# Cook_It.net
KiCad netlist of a schematic drawn in Altium Designer
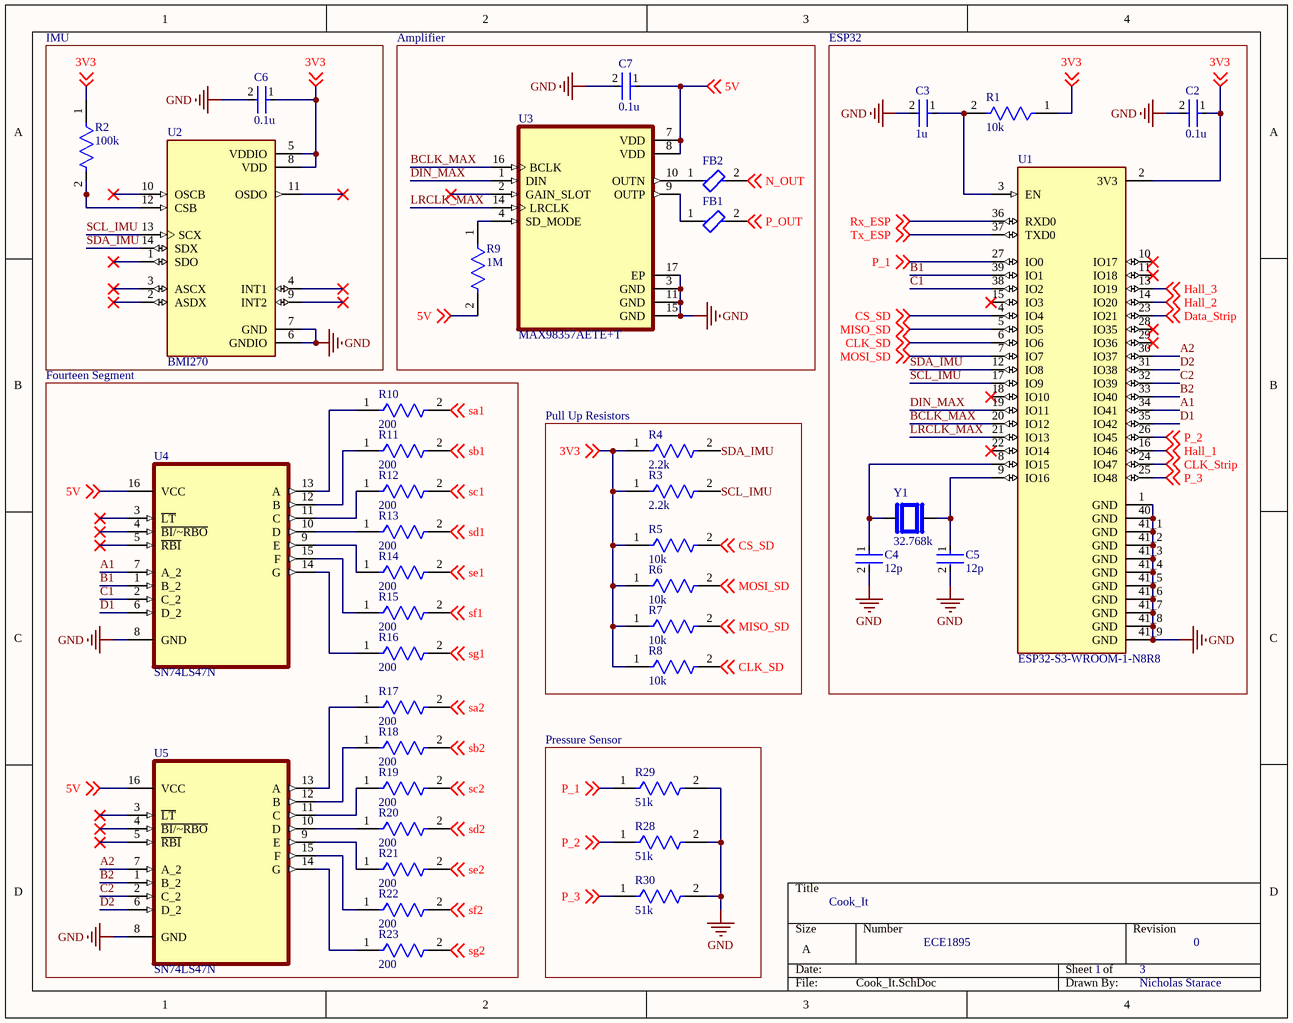
[diagram p0: Cook_It.SchDoc]

(export (version "E")
  (design (tool "Eeschema 10.0.6"))
  (components
    (comp (ref "C2")
      (value "0.1u")
      (footprint "FP-GRM21B-0_2-e0_2_0_7-IPC_B")
      (description "CAP CER 2.2UF 100V X7T 0805")
      (libsource (lib "Altium Content Vault") (part "b4654b650e69147ec39a6b967a45e02"))
    )
    (comp (ref "C3")
      (value "1u")
      (footprint "FP-GRM21B-0_2-e0_2_0_7-IPC_B")
      (description "CAP CER 2.2UF 100V X7T 0805")
      (libsource (lib "Altium Content Vault") (part "b4654b650e69147ec39a6b967a45e02"))
    )
    (comp (ref "C4")
      (value "12p")
      (footprint "FP-GRM21B-0_2-e0_2_0_7-IPC_B")
      (description "CAP CER 2.2UF 100V X7T 0805")
      (libsource (lib "Altium Content Vault") (part "b4654b650e69147ec39a6b967a45e02"))
    )
    (comp (ref "C5")
      (value "12p")
      (footprint "FP-GRM21B-0_2-e0_2_0_7-IPC_B")
      (description "CAP CER 2.2UF 100V X7T 0805")
      (libsource (lib "Altium Content Vault") (part "b4654b650e69147ec39a6b967a45e02"))
    )
    (comp (ref "C6")
      (value "0.1u")
      (footprint "FP-GRM21B-0_2-e0_2_0_7-IPC_B")
      (description "CAP CER 2.2UF 100V X7T 0805")
      (libsource (lib "Altium Content Vault") (part "b4654b650e69147ec39a6b967a45e02"))
    )
    (comp (ref "C7")
      (value "0.1u")
      (footprint "FP-GRM21B-0_2-e0_2_0_7-IPC_B")
      (description "CAP CER 2.2UF 100V X7T 0805")
      (libsource (lib "Altium Content Vault") (part "b4654b650e69147ec39a6b967a45e02"))
    )
    (comp (ref "FB1")
      (value "~")
      (footprint "FP-BMB2A1000LN2-IPC_C")
      (description "FERRITE BEAD 1 KOHM 0805 1LN")
      (fields (field (name "TOLERANCE") "25%"))
      (libsource (lib "Altium Content Vault") (part "5f30dd21d616792df468990f7003faa"))
    )
    (comp (ref "FB2")
      (value "~")
      (footprint "FP-BMB2A1000LN2-IPC_C")
      (description "FERRITE BEAD 1 KOHM 0805 1LN")
      (fields (field (name "TOLERANCE") "25%"))
      (libsource (lib "Altium Content Vault") (part "5f30dd21d616792df468990f7003faa"))
    )
    (comp (ref "R1")
      (value "10k")
      (footprint "FP-TFCR0805-IPC_B")
      (description "RES Thin Film,  499kΩ, 0.1%, 0.125W, 25ppm/°C, 0805")
      (libsource (lib "Altium Content Vault") (part "1029c3af85768c4190bb7ad29bc67b5"))
    )
    (comp (ref "R2")
      (value "100k")
      (footprint "FP-TFCR0805-IPC_B")
      (description "RES Thin Film,  499kΩ, 0.1%, 0.125W, 25ppm/°C, 0805")
      (libsource (lib "Altium Content Vault") (part "1029c3af85768c4190bb7ad29bc67b5"))
    )
    (comp (ref "R3")
      (value "2.2k")
      (footprint "FP-TFCR0805-IPC_B")
      (description "RES Thin Film,  499kΩ, 0.1%, 0.125W, 25ppm/°C, 0805")
      (libsource (lib "Altium Content Vault") (part "1029c3af85768c4190bb7ad29bc67b5"))
    )
    (comp (ref "R4")
      (value "2.2k")
      (footprint "FP-TFCR0805-IPC_B")
      (description "RES Thin Film,  499kΩ, 0.1%, 0.125W, 25ppm/°C, 0805")
      (libsource (lib "Altium Content Vault") (part "1029c3af85768c4190bb7ad29bc67b5"))
    )
    (comp (ref "R5")
      (value "10k")
      (footprint "FP-TFCR0805-IPC_B")
      (description "RES Thin Film,  499kΩ, 0.1%, 0.125W, 25ppm/°C, 0805")
      (libsource (lib "Altium Content Vault") (part "1029c3af85768c4190bb7ad29bc67b5"))
    )
    (comp (ref "R6")
      (value "10k")
      (footprint "FP-TFCR0805-IPC_B")
      (description "RES Thin Film,  499kΩ, 0.1%, 0.125W, 25ppm/°C, 0805")
      (libsource (lib "Altium Content Vault") (part "1029c3af85768c4190bb7ad29bc67b5"))
    )
    (comp (ref "R7")
      (value "10k")
      (footprint "FP-TFCR0805-IPC_B")
      (description "RES Thin Film,  499kΩ, 0.1%, 0.125W, 25ppm/°C, 0805")
      (libsource (lib "Altium Content Vault") (part "1029c3af85768c4190bb7ad29bc67b5"))
    )
    (comp (ref "R8")
      (value "10k")
      (footprint "FP-TFCR0805-IPC_B")
      (description "RES Thin Film,  499kΩ, 0.1%, 0.125W, 25ppm/°C, 0805")
      (libsource (lib "Altium Content Vault") (part "1029c3af85768c4190bb7ad29bc67b5"))
    )
    (comp (ref "R9")
      (value "1M")
      (footprint "FP-TFCR0805-IPC_B")
      (description "RES Thin Film,  499kΩ, 0.1%, 0.125W, 25ppm/°C, 0805")
      (libsource (lib "Altium Content Vault") (part "1029c3af85768c4190bb7ad29bc67b5"))
    )
    (comp (ref "R10")
      (value "200")
      (footprint "FP-TFCR0805-MFG")
      (description "RES Thin Film,  1.72kΩ, 1%, 0.125W, 25ppm/°C, 0805")
      (libsource (lib "Altium Content Vault") (part "1029c3af85768c4190bb7ad29bc67b5"))
    )
    (comp (ref "R11")
      (value "200")
      (footprint "FP-TFCR0805-MFG")
      (description "RES Thin Film,  1.72kΩ, 1%, 0.125W, 25ppm/°C, 0805")
      (libsource (lib "Altium Content Vault") (part "1029c3af85768c4190bb7ad29bc67b5"))
    )
    (comp (ref "R12")
      (value "200")
      (footprint "FP-TFCR0805-MFG")
      (description "RES Thin Film,  1.72kΩ, 1%, 0.125W, 25ppm/°C, 0805")
      (libsource (lib "Altium Content Vault") (part "1029c3af85768c4190bb7ad29bc67b5"))
    )
    (comp (ref "R13")
      (value "200")
      (footprint "FP-TFCR0805-MFG")
      (description "RES Thin Film,  1.72kΩ, 1%, 0.125W, 25ppm/°C, 0805")
      (libsource (lib "Altium Content Vault") (part "1029c3af85768c4190bb7ad29bc67b5"))
    )
    (comp (ref "R14")
      (value "200")
      (footprint "FP-TFCR0805-MFG")
      (description "RES Thin Film,  1.72kΩ, 1%, 0.125W, 25ppm/°C, 0805")
      (libsource (lib "Altium Content Vault") (part "1029c3af85768c4190bb7ad29bc67b5"))
    )
    (comp (ref "R15")
      (value "200")
      (footprint "FP-TFCR0805-MFG")
      (description "RES Thin Film,  1.72kΩ, 1%, 0.125W, 25ppm/°C, 0805")
      (libsource (lib "Altium Content Vault") (part "1029c3af85768c4190bb7ad29bc67b5"))
    )
    (comp (ref "R16")
      (value "200")
      (footprint "FP-TFCR0805-MFG")
      (description "RES Thin Film,  1.72kΩ, 1%, 0.125W, 25ppm/°C, 0805")
      (libsource (lib "Altium Content Vault") (part "1029c3af85768c4190bb7ad29bc67b5"))
    )
    (comp (ref "R17")
      (value "200")
      (footprint "FP-TFCR0805-MFG")
      (description "RES Thin Film,  1.72kΩ, 1%, 0.125W, 25ppm/°C, 0805")
      (libsource (lib "Altium Content Vault") (part "1029c3af85768c4190bb7ad29bc67b5"))
    )
    (comp (ref "R18")
      (value "200")
      (footprint "FP-TFCR0805-MFG")
      (description "RES Thin Film,  1.72kΩ, 1%, 0.125W, 25ppm/°C, 0805")
      (libsource (lib "Altium Content Vault") (part "1029c3af85768c4190bb7ad29bc67b5"))
    )
    (comp (ref "R19")
      (value "200")
      (footprint "FP-TFCR0805-MFG")
      (description "RES Thin Film,  1.72kΩ, 1%, 0.125W, 25ppm/°C, 0805")
      (libsource (lib "Altium Content Vault") (part "1029c3af85768c4190bb7ad29bc67b5"))
    )
    (comp (ref "R20")
      (value "200")
      (footprint "FP-TFCR0805-MFG")
      (description "RES Thin Film,  1.72kΩ, 1%, 0.125W, 25ppm/°C, 0805")
      (libsource (lib "Altium Content Vault") (part "1029c3af85768c4190bb7ad29bc67b5"))
    )
    (comp (ref "R21")
      (value "200")
      (footprint "FP-TFCR0805-MFG")
      (description "RES Thin Film,  1.72kΩ, 1%, 0.125W, 25ppm/°C, 0805")
      (libsource (lib "Altium Content Vault") (part "1029c3af85768c4190bb7ad29bc67b5"))
    )
    (comp (ref "R22")
      (value "200")
      (footprint "FP-TFCR0805-MFG")
      (description "RES Thin Film,  1.72kΩ, 1%, 0.125W, 25ppm/°C, 0805")
      (libsource (lib "Altium Content Vault") (part "1029c3af85768c4190bb7ad29bc67b5"))
    )
    (comp (ref "R23")
      (value "200")
      (footprint "FP-TFCR0805-MFG")
      (description "RES Thin Film,  1.72kΩ, 1%, 0.125W, 25ppm/°C, 0805")
      (libsource (lib "Altium Content Vault") (part "1029c3af85768c4190bb7ad29bc67b5"))
    )
    (comp (ref "R28")
      (value "51k")
      (footprint "FP-TFCR0805-IPC_B")
      (description "RES Thin Film,  499kΩ, 0.1%, 0.125W, 25ppm/°C, 0805")
      (libsource (lib "Altium Content Vault") (part "1029c3af85768c4190bb7ad29bc67b5"))
    )
    (comp (ref "R29")
      (value "51k")
      (footprint "FP-TFCR0805-IPC_B")
      (description "RES Thin Film,  499kΩ, 0.1%, 0.125W, 25ppm/°C, 0805")
      (libsource (lib "Altium Content Vault") (part "1029c3af85768c4190bb7ad29bc67b5"))
    )
    (comp (ref "R30")
      (value "51k")
      (footprint "FP-TFCR0805-IPC_B")
      (description "RES Thin Film,  499kΩ, 0.1%, 0.125W, 25ppm/°C, 0805")
      (libsource (lib "Altium Content Vault") (part "1029c3af85768c4190bb7ad29bc67b5"))
    )
    (comp (ref "U1")
      (value "ESP32-S3-WROOM-1-N8R8")
      (footprint "XCVR_ESP32S3WROOM1N8R8")
      (description "Bluetooth, WiFi 802.11b/g/n, Bluetooth v5.0 Transceiver Module 2.4GHz PCB Trace Surface Mount")
      (fields (field (name "MF") "Espressif Systems"))
      (libsource (lib "ESP32-S3-WROOM-1-N8R8") (part "ESP32-S3-WROOM-1-N8R8"))
    )
    (comp (ref "U2")
      (value "BMI270")
      (footprint "XDCR_BMI270")
      (description "Accelerometer, Gyroscope, 6 Axis Sensor IÂ²C, SPI Output")
      (fields (field (name "DIGI-KEY_PART_NUMBER") "828-1091-2-ND") (field (name "MF") "Bosch Sensortec"))
      (libsource (lib "BMI270") (part "BMI270"))
    )
    (comp (ref "U3")
      (value "MAX98357AETE+T")
      (footprint "QFN50P300X300X80-17N")
      (description "Tiny, Low-Cost, PCM Class D Amplifier with Class AB Performance")
      (fields (field (name "MF") "Analog Devices"))
      (libsource (lib "MAX98357AETE_T") (part "MAX98357AETE+T"))
    )
    (comp (ref "U4")
      (value "SN74LS47N")
      (footprint "SOIC127P600X175-16N")
      (description "Decoder/Driver Single 4-to-7 16-Pin PDIP Tube")
      (fields (field (name "MF") "onsemi"))
      (libsource (lib "SN74LS47N") (part "SN74LS47N"))
    )
    (comp (ref "U5")
      (value "SN74LS47N")
      (footprint "SOIC127P600X175-16N")
      (description "Decoder/Driver Single 4-to-7 16-Pin PDIP Tube")
      (fields (field (name "MF") "onsemi"))
      (libsource (lib "SN74LS47N") (part "SN74LS47N"))
    )
    (comp (ref "Y1")
      (value "32.768k")
      (footprint "XTAL_ABS07-32.768KHZ-T")
      (description "32.768 kHz Â±20ppm Crystal 12.5pF 70 kOhms 2-SMD, No Lead")
      (fields (field (name "MP") "ABS07-32.768KHZ-T") (field (name "MF") "Abracon"))
      (libsource (lib "ABS07-32.768KHZ-T") (part "ABS07-32.768KHZ-T"))
    )
  )
  (nets
    (net (code "1") (name "/A1") (class "Default")
      (node (ref "U1") (pin "34") (pinfunction "IO41_34") (pintype "bidirectional"))
      (node (ref "U4") (pin "7") (pinfunction "A_2_7") (pintype "input"))
    )
    (net (code "2") (name "/A2") (class "Default")
      (node (ref "U1") (pin "30") (pinfunction "IO37_30") (pintype "bidirectional"))
      (node (ref "U5") (pin "7") (pinfunction "A_2_7") (pintype "input"))
    )
    (net (code "3") (name "/B1") (class "Default")
      (node (ref "U1") (pin "39") (pinfunction "IO1_39") (pintype "bidirectional"))
      (node (ref "U4") (pin "1") (pinfunction "B_2_1") (pintype "input"))
    )
    (net (code "4") (name "/B2") (class "Default")
      (node (ref "U1") (pin "33") (pinfunction "IO40_33") (pintype "bidirectional"))
      (node (ref "U5") (pin "1") (pinfunction "B_2_1") (pintype "input"))
    )
    (net (code "5") (name "/BCLK_MAX") (class "Default")
      (node (ref "U1") (pin "20") (pinfunction "IO12_20") (pintype "bidirectional"))
      (node (ref "U3") (pin "16") (pinfunction "BCLK_16") (pintype "input"))
    )
    (net (code "6") (name "/C1") (class "Default")
      (node (ref "U1") (pin "38") (pinfunction "IO2_38") (pintype "bidirectional"))
      (node (ref "U4") (pin "2") (pinfunction "C_2_2") (pintype "input"))
    )
    (net (code "7") (name "/C2") (class "Default")
      (node (ref "U1") (pin "32") (pinfunction "IO39_32") (pintype "bidirectional"))
      (node (ref "U5") (pin "2") (pinfunction "C_2_2") (pintype "input"))
    )
    (net (code "8") (name "/D1") (class "Default")
      (node (ref "U1") (pin "35") (pinfunction "IO42_35") (pintype "bidirectional"))
      (node (ref "U4") (pin "6") (pinfunction "D_2_6") (pintype "input"))
    )
    (net (code "9") (name "/D2") (class "Default")
      (node (ref "U1") (pin "31") (pinfunction "IO38_31") (pintype "bidirectional"))
      (node (ref "U5") (pin "6") (pinfunction "D_2_6") (pintype "input"))
    )
    (net (code "10") (name "/DIN_MAX") (class "Default")
      (node (ref "U1") (pin "19") (pinfunction "IO11_19") (pintype "bidirectional"))
      (node (ref "U3") (pin "1") (pinfunction "DIN_1") (pintype "input"))
    )
    (net (code "11") (name "/LRCLK_MAX") (class "Default")
      (node (ref "U1") (pin "21") (pinfunction "IO13_21") (pintype "bidirectional"))
      (node (ref "U3") (pin "14") (pinfunction "LRCLK_14") (pintype "input"))
    )
    (net (code "12") (name "/SCL_IMU") (class "Default")
      (node (ref "R3") (pin "2") (pinfunction "2_2") (pintype "passive"))
      (node (ref "U1") (pin "17") (pinfunction "IO9_17") (pintype "bidirectional"))
      (node (ref "U2") (pin "13") (pinfunction "SCX_13") (pintype "input"))
    )
    (net (code "13") (name "/SDA_IMU") (class "Default")
      (node (ref "R4") (pin "2") (pinfunction "2_2") (pintype "passive"))
      (node (ref "U1") (pin "12") (pinfunction "IO8_12") (pintype "bidirectional"))
      (node (ref "U2") (pin "14") (pinfunction "SDX_14") (pintype "bidirectional"))
    )
    (net (code "14") (name "3V3") (class "Default")
      (node (ref "C2") (pin "1") (pinfunction "1_1") (pintype "passive"))
      (node (ref "C6") (pin "1") (pinfunction "1_1") (pintype "passive"))
      (node (ref "R1") (pin "1") (pinfunction "1_1") (pintype "passive"))
      (node (ref "R2") (pin "1") (pinfunction "1_1") (pintype "passive"))
      (node (ref "R3") (pin "1") (pinfunction "1_1") (pintype "passive"))
      (node (ref "R4") (pin "1") (pinfunction "1_1") (pintype "passive"))
      (node (ref "R5") (pin "1") (pinfunction "1_1") (pintype "passive"))
      (node (ref "R6") (pin "1") (pinfunction "1_1") (pintype "passive"))
      (node (ref "R7") (pin "1") (pinfunction "1_1") (pintype "passive"))
      (node (ref "R8") (pin "1") (pinfunction "1_1") (pintype "passive"))
      (node (ref "U1") (pin "2") (pinfunction "3V3_2") (pintype "power_in"))
      (node (ref "U2") (pin "5") (pinfunction "VDDIO_5") (pintype "power_in"))
      (node (ref "U2") (pin "8") (pinfunction "VDD_8") (pintype "power_in"))
    )
    (net (code "15") (name "5V") (class "Default")
      (node (ref "C7") (pin "1") (pinfunction "1_1") (pintype "passive"))
      (node (ref "R9") (pin "2") (pinfunction "2_2") (pintype "passive"))
      (node (ref "U3") (pin "7") (pinfunction "VDD_7") (pintype "power_in"))
      (node (ref "U3") (pin "8") (pinfunction "VDD_8") (pintype "power_in"))
      (node (ref "U4") (pin "16") (pinfunction "VCC_16") (pintype "power_in"))
      (node (ref "U5") (pin "16") (pinfunction "VCC_16") (pintype "power_in"))
    )
    (net (code "16") (name "CLK_SD") (class "Default")
      (node (ref "R8") (pin "2") (pinfunction "2_2") (pintype "passive"))
      (node (ref "U1") (pin "6") (pinfunction "IO6_6") (pintype "bidirectional"))
    )
    (net (code "17") (name "CLK_Strip") (class "Default")
      (node (ref "U1") (pin "24") (pinfunction "IO47_24") (pintype "bidirectional"))
    )
    (net (code "18") (name "CS_SD") (class "Default")
      (node (ref "R5") (pin "2") (pinfunction "2_2") (pintype "passive"))
      (node (ref "U1") (pin "4") (pinfunction "IO4_4") (pintype "bidirectional"))
    )
    (net (code "19") (name "Data_Strip") (class "Default")
      (node (ref "U1") (pin "23") (pinfunction "IO21_23") (pintype "bidirectional"))
    )
    (net (code "20") (name "GND") (class "Default")
      (node (ref "C2") (pin "2") (pinfunction "2_2") (pintype "passive"))
      (node (ref "C3") (pin "2") (pinfunction "2_2") (pintype "passive"))
      (node (ref "C4") (pin "2") (pinfunction "2_2") (pintype "passive"))
      (node (ref "C5") (pin "2") (pinfunction "2_2") (pintype "passive"))
      (node (ref "C6") (pin "2") (pinfunction "2_2") (pintype "passive"))
      (node (ref "C7") (pin "2") (pinfunction "2_2") (pintype "passive"))
      (node (ref "R28") (pin "2") (pinfunction "2_2") (pintype "passive"))
      (node (ref "R29") (pin "2") (pinfunction "2_2") (pintype "passive"))
      (node (ref "R30") (pin "2") (pinfunction "2_2") (pintype "passive"))
      (node (ref "U1") (pin "1") (pinfunction "GND_1") (pintype "power_in"))
      (node (ref "U1") (pin "40") (pinfunction "GND_40") (pintype "power_in"))
      (node (ref "U1") (pin "41_1") (pinfunction "GND_41_1") (pintype "power_in"))
      (node (ref "U1") (pin "41_2") (pinfunction "GND_41_2") (pintype "power_in"))
      (node (ref "U1") (pin "41_3") (pinfunction "GND_41_3") (pintype "power_in"))
      (node (ref "U1") (pin "41_4") (pinfunction "GND_41_4") (pintype "power_in"))
      (node (ref "U1") (pin "41_5") (pinfunction "GND_41_5") (pintype "power_in"))
      (node (ref "U1") (pin "41_6") (pinfunction "GND_41_6") (pintype "power_in"))
      (node (ref "U1") (pin "41_7") (pinfunction "GND_41_7") (pintype "power_in"))
      (node (ref "U1") (pin "41_8") (pinfunction "GND_41_8") (pintype "power_in"))
      (node (ref "U1") (pin "41_9") (pinfunction "GND_41_9") (pintype "power_in"))
      (node (ref "U2") (pin "6") (pinfunction "GNDIO_6") (pintype "power_in"))
      (node (ref "U2") (pin "7") (pinfunction "GND_7") (pintype "power_in"))
      (node (ref "U3") (pin "11") (pinfunction "GND_11") (pintype "power_in"))
      (node (ref "U3") (pin "15") (pinfunction "GND_15") (pintype "power_in"))
      (node (ref "U3") (pin "17") (pinfunction "EP_17") (pintype "power_in"))
      (node (ref "U3") (pin "3") (pinfunction "GND_3") (pintype "power_in"))
      (node (ref "U4") (pin "8") (pinfunction "GND_8") (pintype "passive"))
      (node (ref "U5") (pin "8") (pinfunction "GND_8") (pintype "passive"))
    )
    (net (code "21") (name "Hall_1") (class "Default")
      (node (ref "U1") (pin "16") (pinfunction "IO46_16") (pintype "bidirectional"))
    )
    (net (code "22") (name "Hall_2") (class "Default")
      (node (ref "U1") (pin "14") (pinfunction "IO20_14") (pintype "bidirectional"))
    )
    (net (code "23") (name "Hall_3") (class "Default")
      (node (ref "U1") (pin "13") (pinfunction "IO19_13") (pintype "bidirectional"))
    )
    (net (code "24") (name "MISO_SD") (class "Default")
      (node (ref "R7") (pin "2") (pinfunction "2_2") (pintype "passive"))
      (node (ref "U1") (pin "5") (pinfunction "IO5_5") (pintype "bidirectional"))
    )
    (net (code "25") (name "MOSI_SD") (class "Default")
      (node (ref "R6") (pin "2") (pinfunction "2_2") (pintype "passive"))
      (node (ref "U1") (pin "7") (pinfunction "IO7_7") (pintype "bidirectional"))
    )
    (net (code "26") (name "N_OUT") (class "Default")
      (node (ref "FB2") (pin "2") (pinfunction "2_2") (pintype "passive"))
    )
    (net (code "27") (name "Net-(U1-EN)") (class "Default")
      (node (ref "C3") (pin "1") (pinfunction "1_1") (pintype "passive"))
      (node (ref "R1") (pin "2") (pinfunction "2_2") (pintype "passive"))
      (node (ref "U1") (pin "3") (pinfunction "EN_3") (pintype "input"))
    )
    (net (code "28") (name "Net-(U1-IO15)") (class "Default")
      (node (ref "C4") (pin "1") (pinfunction "1_1") (pintype "passive"))
      (node (ref "U1") (pin "8") (pinfunction "IO15_8") (pintype "bidirectional"))
      (node (ref "Y1") (pin "2") (pinfunction "2_2") (pintype "passive"))
    )
    (net (code "29") (name "Net-(U1-IO16)") (class "Default")
      (node (ref "C5") (pin "1") (pinfunction "1_1") (pintype "passive"))
      (node (ref "U1") (pin "9") (pinfunction "IO16_9") (pintype "bidirectional"))
      (node (ref "Y1") (pin "1") (pinfunction "1_1") (pintype "passive"))
    )
    (net (code "30") (name "Net-(U2-CSB)") (class "Default")
      (node (ref "R2") (pin "2") (pinfunction "2_2") (pintype "passive"))
      (node (ref "U2") (pin "12") (pinfunction "CSB_12") (pintype "input"))
    )
    (net (code "31") (name "Net-(U3-OUTN)") (class "Default")
      (node (ref "FB2") (pin "1") (pinfunction "1_1") (pintype "passive"))
      (node (ref "U3") (pin "10") (pinfunction "OUTN_10") (pintype "output"))
    )
    (net (code "32") (name "Net-(U3-OUTP)") (class "Default")
      (node (ref "FB1") (pin "1") (pinfunction "1_1") (pintype "passive"))
      (node (ref "U3") (pin "9") (pinfunction "OUTP_9") (pintype "output"))
    )
    (net (code "33") (name "Net-(U3-SD_MODE)") (class "Default")
      (node (ref "R9") (pin "1") (pinfunction "1_1") (pintype "passive"))
      (node (ref "U3") (pin "4") (pinfunction "SD_MODE_4") (pintype "input"))
    )
    (net (code "34") (name "Net-(U4-A)") (class "Default")
      (node (ref "R10") (pin "1") (pinfunction "1_1") (pintype "passive"))
      (node (ref "U4") (pin "13") (pinfunction "A_13") (pintype "output"))
    )
    (net (code "35") (name "Net-(U4-B)") (class "Default")
      (node (ref "R11") (pin "1") (pinfunction "1_1") (pintype "passive"))
      (node (ref "U4") (pin "12") (pinfunction "B_12") (pintype "output"))
    )
    (net (code "36") (name "Net-(U4-C)") (class "Default")
      (node (ref "R12") (pin "1") (pinfunction "1_1") (pintype "passive"))
      (node (ref "U4") (pin "11") (pinfunction "C_11") (pintype "output"))
    )
    (net (code "37") (name "Net-(U4-D)") (class "Default")
      (node (ref "R13") (pin "1") (pinfunction "1_1") (pintype "passive"))
      (node (ref "U4") (pin "10") (pinfunction "D_10") (pintype "output"))
    )
    (net (code "38") (name "Net-(U4-E)") (class "Default")
      (node (ref "R14") (pin "1") (pinfunction "1_1") (pintype "passive"))
      (node (ref "U4") (pin "9") (pinfunction "E_9") (pintype "output"))
    )
    (net (code "39") (name "Net-(U4-F)") (class "Default")
      (node (ref "R15") (pin "1") (pinfunction "1_1") (pintype "passive"))
      (node (ref "U4") (pin "15") (pinfunction "F_15") (pintype "output"))
    )
    (net (code "40") (name "Net-(U4-G)") (class "Default")
      (node (ref "R16") (pin "1") (pinfunction "1_1") (pintype "passive"))
      (node (ref "U4") (pin "14") (pinfunction "G_14") (pintype "output"))
    )
    (net (code "41") (name "Net-(U5-A)") (class "Default")
      (node (ref "R17") (pin "1") (pinfunction "1_1") (pintype "passive"))
      (node (ref "U5") (pin "13") (pinfunction "A_13") (pintype "output"))
    )
    (net (code "42") (name "Net-(U5-B)") (class "Default")
      (node (ref "R18") (pin "1") (pinfunction "1_1") (pintype "passive"))
      (node (ref "U5") (pin "12") (pinfunction "B_12") (pintype "output"))
    )
    (net (code "43") (name "Net-(U5-C)") (class "Default")
      (node (ref "R19") (pin "1") (pinfunction "1_1") (pintype "passive"))
      (node (ref "U5") (pin "11") (pinfunction "C_11") (pintype "output"))
    )
    (net (code "44") (name "Net-(U5-D)") (class "Default")
      (node (ref "R20") (pin "1") (pinfunction "1_1") (pintype "passive"))
      (node (ref "U5") (pin "10") (pinfunction "D_10") (pintype "output"))
    )
    (net (code "45") (name "Net-(U5-E)") (class "Default")
      (node (ref "R21") (pin "1") (pinfunction "1_1") (pintype "passive"))
      (node (ref "U5") (pin "9") (pinfunction "E_9") (pintype "output"))
    )
    (net (code "46") (name "Net-(U5-F)") (class "Default")
      (node (ref "R22") (pin "1") (pinfunction "1_1") (pintype "passive"))
      (node (ref "U5") (pin "15") (pinfunction "F_15") (pintype "output"))
    )
    (net (code "47") (name "Net-(U5-G)") (class "Default")
      (node (ref "R23") (pin "1") (pinfunction "1_1") (pintype "passive"))
      (node (ref "U5") (pin "14") (pinfunction "G_14") (pintype "output"))
    )
    (net (code "48") (name "P_1") (class "Default")
      (node (ref "R29") (pin "1") (pinfunction "1_1") (pintype "passive"))
      (node (ref "U1") (pin "27") (pinfunction "IO0_27") (pintype "bidirectional"))
    )
    (net (code "49") (name "P_2") (class "Default")
      (node (ref "R28") (pin "1") (pinfunction "1_1") (pintype "passive"))
      (node (ref "U1") (pin "26") (pinfunction "IO45_26") (pintype "bidirectional"))
    )
    (net (code "50") (name "P_3") (class "Default")
      (node (ref "R30") (pin "1") (pinfunction "1_1") (pintype "passive"))
      (node (ref "U1") (pin "25") (pinfunction "IO48_25") (pintype "bidirectional"))
    )
    (net (code "51") (name "P_OUT") (class "Default")
      (node (ref "FB1") (pin "2") (pinfunction "2_2") (pintype "passive"))
    )
    (net (code "52") (name "Rx_ESP") (class "Default")
      (node (ref "U1") (pin "36") (pinfunction "RXD0_36") (pintype "bidirectional"))
    )
    (net (code "53") (name "Tx_ESP") (class "Default")
      (node (ref "U1") (pin "37") (pinfunction "TXD0_37") (pintype "bidirectional"))
    )
    (net (code "54") (name "sa1") (class "Default")
      (node (ref "R10") (pin "2") (pinfunction "2_2") (pintype "passive"))
    )
    (net (code "55") (name "sa2") (class "Default")
      (node (ref "R17") (pin "2") (pinfunction "2_2") (pintype "passive"))
    )
    (net (code "56") (name "sb1") (class "Default")
      (node (ref "R11") (pin "2") (pinfunction "2_2") (pintype "passive"))
    )
    (net (code "57") (name "sb2") (class "Default")
      (node (ref "R18") (pin "2") (pinfunction "2_2") (pintype "passive"))
    )
    (net (code "58") (name "sc1") (class "Default")
      (node (ref "R12") (pin "2") (pinfunction "2_2") (pintype "passive"))
    )
    (net (code "59") (name "sc2") (class "Default")
      (node (ref "R19") (pin "2") (pinfunction "2_2") (pintype "passive"))
    )
    (net (code "60") (name "sd1") (class "Default")
      (node (ref "R13") (pin "2") (pinfunction "2_2") (pintype "passive"))
    )
    (net (code "61") (name "sd2") (class "Default")
      (node (ref "R20") (pin "2") (pinfunction "2_2") (pintype "passive"))
    )
    (net (code "62") (name "se1") (class "Default")
      (node (ref "R14") (pin "2") (pinfunction "2_2") (pintype "passive"))
    )
    (net (code "63") (name "se2") (class "Default")
      (node (ref "R21") (pin "2") (pinfunction "2_2") (pintype "passive"))
    )
    (net (code "64") (name "sf1") (class "Default")
      (node (ref "R15") (pin "2") (pinfunction "2_2") (pintype "passive"))
    )
    (net (code "65") (name "sf2") (class "Default")
      (node (ref "R22") (pin "2") (pinfunction "2_2") (pintype "passive"))
    )
    (net (code "66") (name "sg1") (class "Default")
      (node (ref "R16") (pin "2") (pinfunction "2_2") (pintype "passive"))
    )
    (net (code "67") (name "sg2") (class "Default")
      (node (ref "R23") (pin "2") (pinfunction "2_2") (pintype "passive"))
    )
    (net (code "68") (name "unconnected-(U1-IO3-Pad15)") (class "Default")
      (node (ref "U1") (pin "15") (pinfunction "IO3_15") (pintype "bidirectional+no_connect"))
    )
    (net (code "69") (name "unconnected-(U1-IO10-Pad18)") (class "Default")
      (node (ref "U1") (pin "18") (pinfunction "IO10_18") (pintype "bidirectional+no_connect"))
    )
    (net (code "70") (name "unconnected-(U1-IO14-Pad22)") (class "Default")
      (node (ref "U1") (pin "22") (pinfunction "IO14_22") (pintype "bidirectional+no_connect"))
    )
    (net (code "71") (name "unconnected-(U1-IO17-Pad10)") (class "Default")
      (node (ref "U1") (pin "10") (pinfunction "IO17_10") (pintype "bidirectional+no_connect"))
    )
    (net (code "72") (name "unconnected-(U1-IO18-Pad11)") (class "Default")
      (node (ref "U1") (pin "11") (pinfunction "IO18_11") (pintype "bidirectional+no_connect"))
    )
    (net (code "73") (name "unconnected-(U1-IO35-Pad28)") (class "Default")
      (node (ref "U1") (pin "28") (pinfunction "IO35_28") (pintype "bidirectional+no_connect"))
    )
    (net (code "74") (name "unconnected-(U1-IO36-Pad29)") (class "Default")
      (node (ref "U1") (pin "29") (pinfunction "IO36_29") (pintype "bidirectional+no_connect"))
    )
    (net (code "75") (name "unconnected-(U2-ASCX-Pad3)") (class "Default")
      (node (ref "U2") (pin "3") (pinfunction "ASCX_3") (pintype "bidirectional+no_connect"))
    )
    (net (code "76") (name "unconnected-(U2-ASDX-Pad2)") (class "Default")
      (node (ref "U2") (pin "2") (pinfunction "ASDX_2") (pintype "bidirectional+no_connect"))
    )
    (net (code "77") (name "unconnected-(U2-INT1-Pad4)") (class "Default")
      (node (ref "U2") (pin "4") (pinfunction "INT1_4") (pintype "bidirectional+no_connect"))
    )
    (net (code "78") (name "unconnected-(U2-INT2-Pad9)") (class "Default")
      (node (ref "U2") (pin "9") (pinfunction "INT2_9") (pintype "bidirectional+no_connect"))
    )
    (net (code "79") (name "unconnected-(U2-OSCB-Pad10)") (class "Default")
      (node (ref "U2") (pin "10") (pinfunction "OSCB_10") (pintype "input+no_connect"))
    )
    (net (code "80") (name "unconnected-(U2-OSDO-Pad11)") (class "Default")
      (node (ref "U2") (pin "11") (pinfunction "OSDO_11") (pintype "output+no_connect"))
    )
    (net (code "81") (name "unconnected-(U2-SDO-Pad1)") (class "Default")
      (node (ref "U2") (pin "1") (pinfunction "SDO_1") (pintype "bidirectional+no_connect"))
    )
    (net (code "82") (name "unconnected-(U3-GAIN_SLOT-Pad2)") (class "Default")
      (node (ref "U3") (pin "2") (pinfunction "GAIN_SLOT_2") (pintype "input+no_connect"))
    )
    (net (code "83") (name "unconnected-(U4-~{BI{slash}~RBO}-Pad4)") (class "Default")
      (node (ref "U4") (pin "4") (pinfunction "~{BI/~RBO}_4") (pintype "input+no_connect"))
    )
    (net (code "84") (name "unconnected-(U4-~{LT}-Pad3)") (class "Default")
      (node (ref "U4") (pin "3") (pinfunction "~{LT}_3") (pintype "input+no_connect"))
    )
    (net (code "85") (name "unconnected-(U4-~{RBI}-Pad5)") (class "Default")
      (node (ref "U4") (pin "5") (pinfunction "~{RBI}_5") (pintype "input+no_connect"))
    )
    (net (code "86") (name "unconnected-(U5-~{BI{slash}~RBO}-Pad4)") (class "Default")
      (node (ref "U5") (pin "4") (pinfunction "~{BI/~RBO}_4") (pintype "input+no_connect"))
    )
    (net (code "87") (name "unconnected-(U5-~{LT}-Pad3)") (class "Default")
      (node (ref "U5") (pin "3") (pinfunction "~{LT}_3") (pintype "input+no_connect"))
    )
    (net (code "88") (name "unconnected-(U5-~{RBI}-Pad5)") (class "Default")
      (node (ref "U5") (pin "5") (pinfunction "~{RBI}_5") (pintype "input+no_connect"))
    )
  )
)
